# OpenChargeport_SI4010.net
KiCad netlist of a schematic drawn in EAGLE
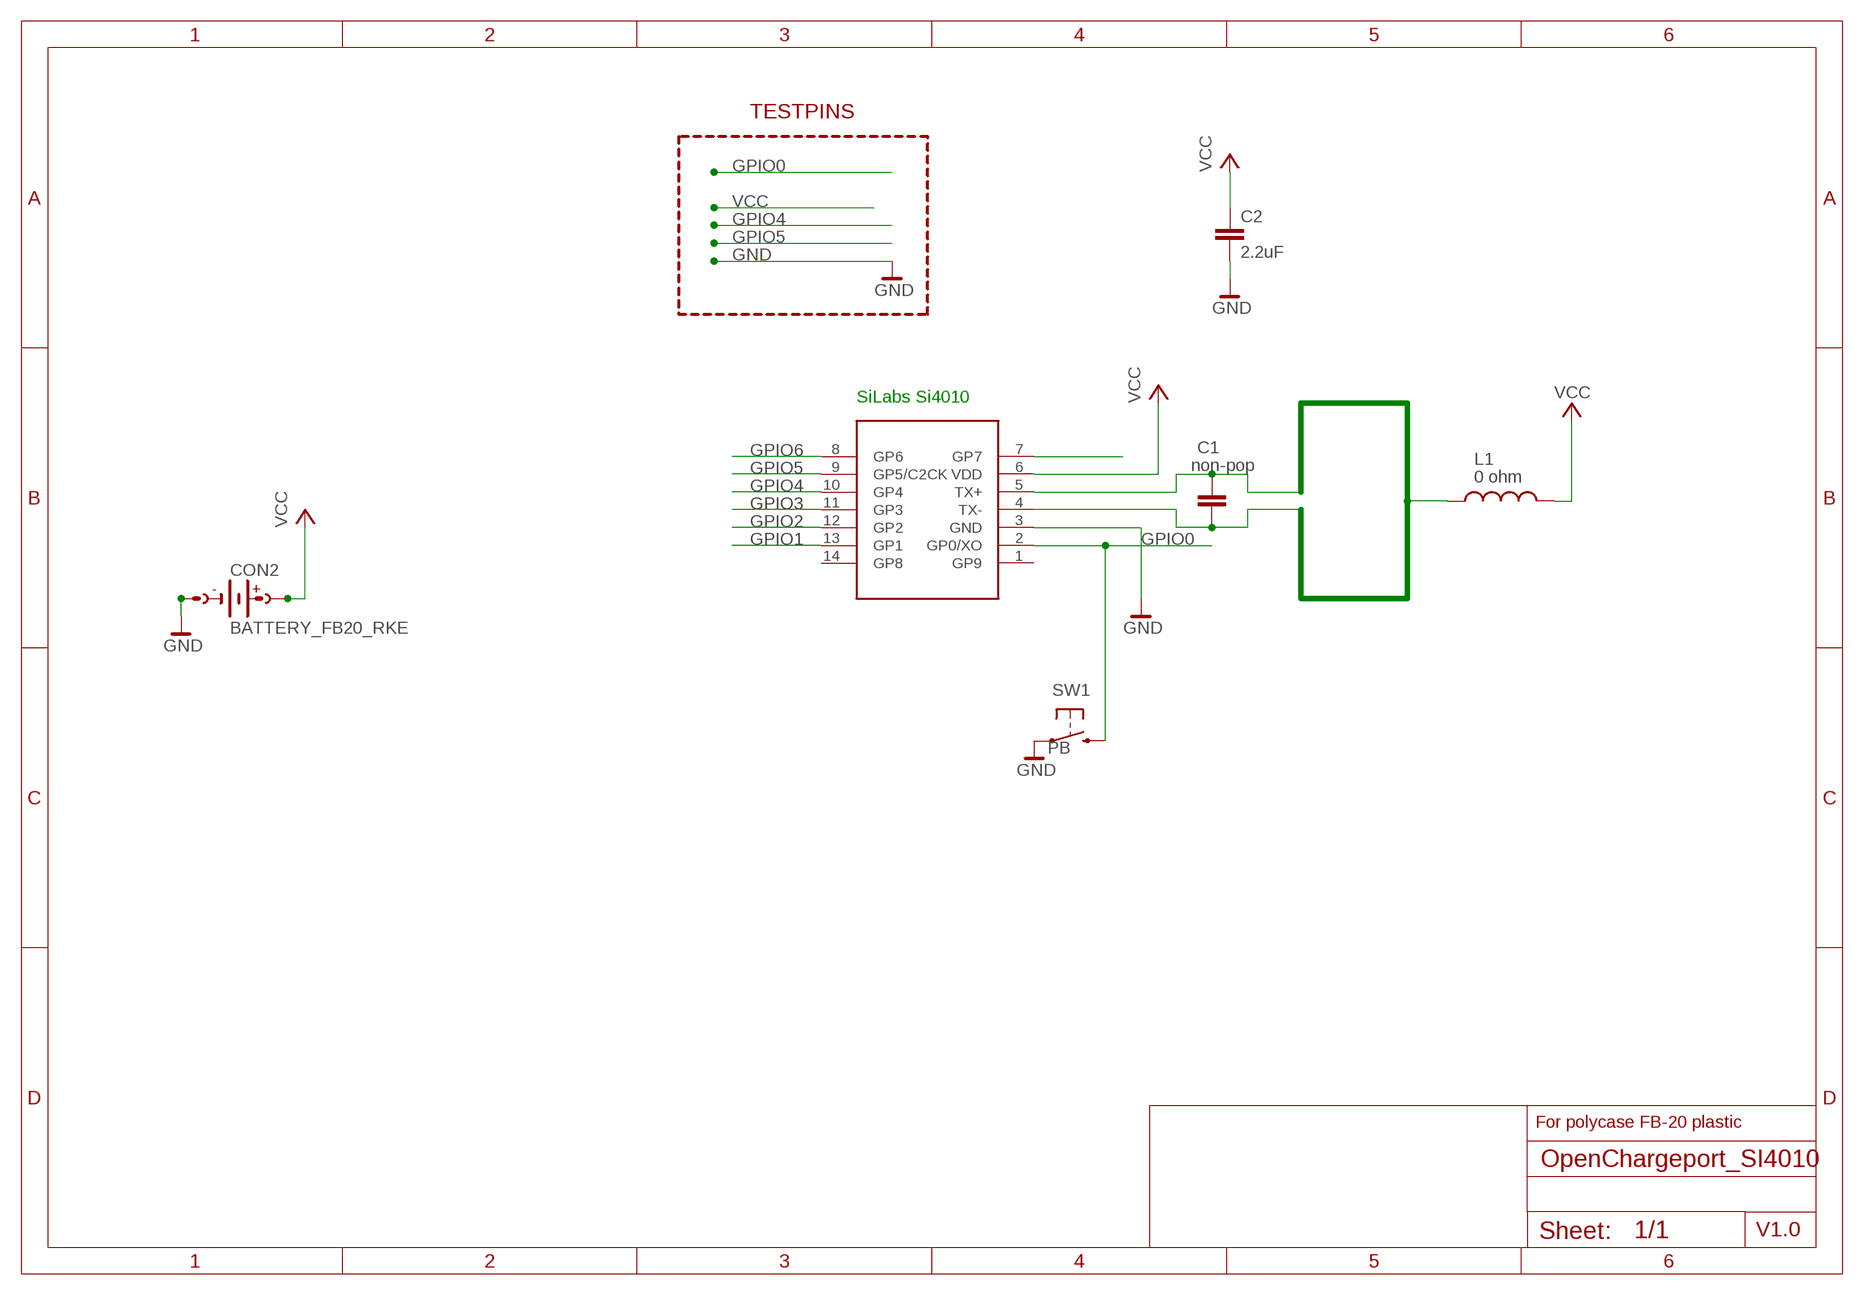
[diagram p0: schematic, sheet 1]

(export (version "E")
  (design (tool "Eeschema 10.0.6"))
  (components
    (comp (ref "C1")
      (value "non-pop")
      (footprint "eagle-import:C0603K")
      (libsource (lib "eagle-import") (part "C-EUC0603K"))
    )
    (comp (ref "C2")
      (value "2.2uF")
      (footprint "eagle-import:C0805K")
      (libsource (lib "eagle-import") (part "C-EUC0805K"))
    )
    (comp (ref "CON2")
      (value "BATTERY_FB20_RKE")
      (footprint "eagle-import:BATTERY_HOLDER_CR2032F_RKE_FB20")
      (libsource (lib "eagle-import") (part "BATTERY_FB20_RKEFB20"))
    )
    (comp (ref "IC1")
      (value "SI4010")
      (footprint "eagle-import:SOIC-14")
      (libsource (lib "eagle-import") (part "SI4010SOIC-14"))
    )
    (comp (ref "L1")
      (value "0 ohm")
      (footprint "eagle-import:L0402")
      (libsource (lib "eagle-import") (part "INDUCTL0402"))
    )
    (comp (ref "SW1")
      (value "PB")
      (footprint "eagle-import:PUSHB_PILL")
      (libsource (lib "eagle-import") (part "PUSHBUTTON1PILL"))
    )
  )
  (nets
    (net (code "1") (name "/GPIO0") (class "Default")
      (node (ref "IC1") (pin "2") (pinfunction "GP0/XO_2") (pintype "bidirectional"))
      (node (ref "SW1") (pin "P$2") (pinfunction "2_P$2") (pintype "passive"))
    )
    (net (code "2") (name "/GPIO1") (class "Default")
      (node (ref "IC1") (pin "13") (pinfunction "GP1_13") (pintype "bidirectional"))
    )
    (net (code "3") (name "/GPIO2") (class "Default")
      (node (ref "IC1") (pin "12") (pinfunction "GP2_12") (pintype "bidirectional"))
    )
    (net (code "4") (name "/GPIO3") (class "Default")
      (node (ref "IC1") (pin "11") (pinfunction "GP3_11") (pintype "bidirectional"))
    )
    (net (code "5") (name "/GPIO4") (class "Default")
      (node (ref "IC1") (pin "10") (pinfunction "GP4_10") (pintype "bidirectional"))
    )
    (net (code "6") (name "/GPIO5") (class "Default")
      (node (ref "IC1") (pin "9") (pinfunction "GP5/C2CK_9") (pintype "bidirectional"))
    )
    (net (code "7") (name "/GPIO6") (class "Default")
      (node (ref "IC1") (pin "8") (pinfunction "GP6_8") (pintype "bidirectional"))
    )
    (net (code "8") (name "GND") (class "Default")
      (node (ref "C2") (pin "2") (pinfunction "2_2") (pintype "passive"))
      (node (ref "CON2") (pin "MINUS") (pinfunction "NEG_MINUS") (pintype "bidirectional"))
      (node (ref "CON2") (pin "MINUS1") (pinfunction "NEG1_MINUS1") (pintype "bidirectional"))
      (node (ref "IC1") (pin "3") (pinfunction "GND_3") (pintype "bidirectional"))
      (node (ref "SW1") (pin "P$1") (pinfunction "1_P$1") (pintype "passive"))
    )
    (net (code "9") (name "Net-(IC1-TX+)") (class "Default")
      (node (ref "C1") (pin "1") (pinfunction "1_1") (pintype "passive"))
      (node (ref "C1") (pin "2") (pinfunction "2_2") (pintype "passive"))
      (node (ref "IC1") (pin "4") (pinfunction "TX-_4") (pintype "bidirectional"))
      (node (ref "IC1") (pin "5") (pinfunction "TX+_5") (pintype "bidirectional"))
      (node (ref "L1") (pin "1") (pinfunction "1_1") (pintype "passive"))
    )
    (net (code "10") (name "VCC") (class "Default")
      (node (ref "C2") (pin "1") (pinfunction "1_1") (pintype "passive"))
      (node (ref "CON2") (pin "PLUS1") (pinfunction "POS_PLUS1") (pintype "bidirectional"))
      (node (ref "CON2") (pin "PLUS2") (pinfunction "POS1_PLUS2") (pintype "bidirectional"))
      (node (ref "IC1") (pin "6") (pinfunction "VDD_6") (pintype "bidirectional"))
      (node (ref "L1") (pin "2") (pinfunction "2_2") (pintype "passive"))
    )
    (net (code "11") (name "unconnected-(IC1-GP7-Pad7)") (class "Default")
      (node (ref "IC1") (pin "7") (pinfunction "GP7_7") (pintype "bidirectional"))
    )
    (net (code "12") (name "unconnected-(IC1-GP8-Pad14)") (class "Default")
      (node (ref "IC1") (pin "14") (pinfunction "GP8_14") (pintype "bidirectional"))
    )
    (net (code "13") (name "unconnected-(IC1-GP9-Pad1)") (class "Default")
      (node (ref "IC1") (pin "1") (pinfunction "GP9_1") (pintype "bidirectional"))
    )
  )
)
